# GraphicDisplay.net
KiCad netlist of a schematic drawn in EAGLE
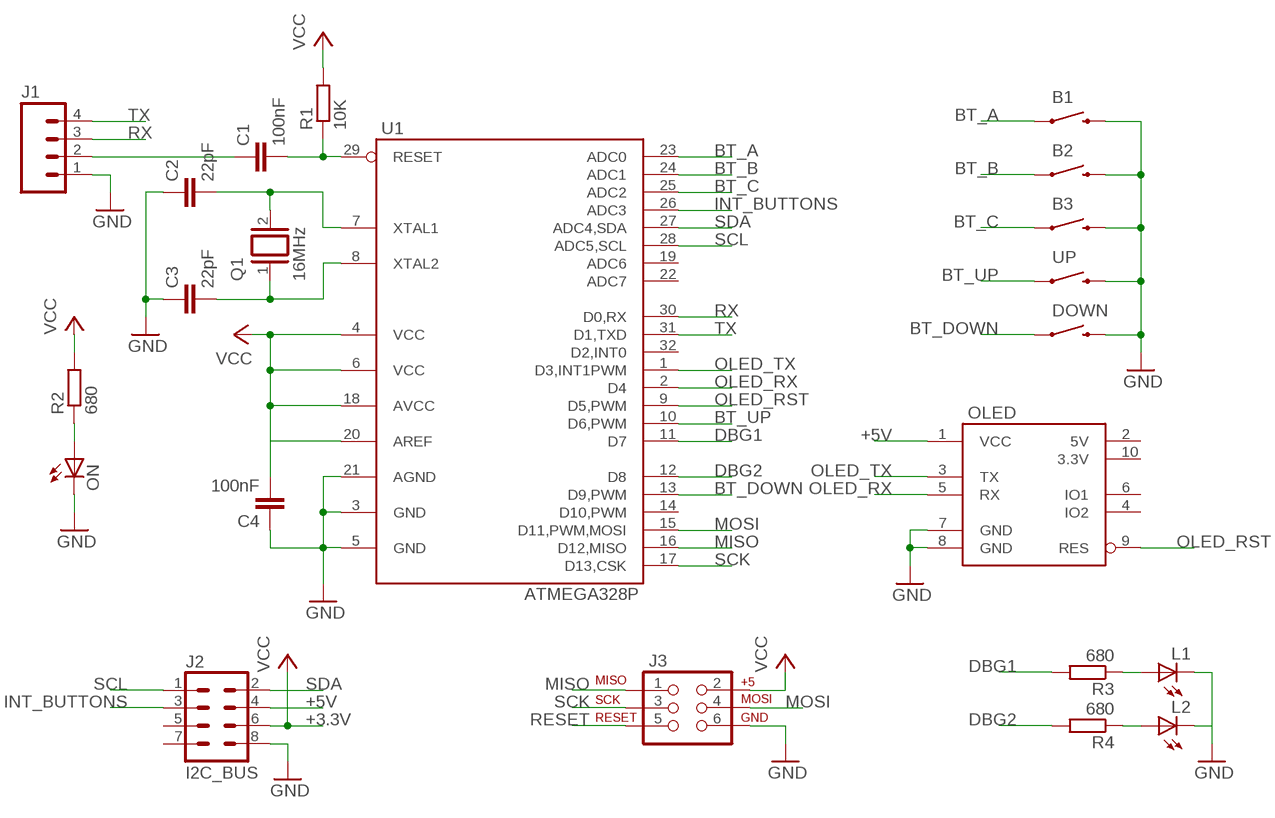
[diagram p0: schematic, sheet 1]

(export (version "E")
  (design (tool "Eeschema 10.0.6"))
  (components
    (comp (ref "B1")
      (value "SWITCH-MOMENTARY-212MM")
      (footprint "eagle-import:TACTILE-PTH-12MM")
      (libsource (lib "eagle-import") (part "SWITCH-MOMENTARY-212MM"))
    )
    (comp (ref "B2")
      (value "SWITCH-MOMENTARY-212MM")
      (footprint "eagle-import:TACTILE-PTH-12MM")
      (libsource (lib "eagle-import") (part "SWITCH-MOMENTARY-212MM"))
    )
    (comp (ref "B3")
      (value "SWITCH-MOMENTARY-212MM")
      (footprint "eagle-import:TACTILE-PTH-12MM")
      (libsource (lib "eagle-import") (part "SWITCH-MOMENTARY-212MM"))
    )
    (comp (ref "C1")
      (value "100nF")
      (footprint "eagle-import:C0805")
      (libsource (lib "eagle-import") (part "C-EUC0805"))
    )
    (comp (ref "C2")
      (value "22pF")
      (footprint "eagle-import:C0805")
      (libsource (lib "eagle-import") (part "C-EUC0805"))
    )
    (comp (ref "C3")
      (value "22pF")
      (footprint "eagle-import:C0805")
      (libsource (lib "eagle-import") (part "C-EUC0805"))
    )
    (comp (ref "C4")
      (value "100nF")
      (footprint "eagle-import:C0805")
      (libsource (lib "eagle-import") (part "C-EUC0805"))
    )
    (comp (ref "DOWN")
      (value "SWITCH-MOMENTARY-212MM")
      (footprint "eagle-import:TACTILE-PTH-12MM")
      (libsource (lib "eagle-import") (part "SWITCH-MOMENTARY-212MM"))
    )
    (comp (ref "J1")
      (value "M04PTH")
      (footprint "eagle-import:1X04")
      (libsource (lib "eagle-import") (part "M04PTH"))
    )
    (comp (ref "J2")
      (value "I2C_BUS")
      (footprint "eagle-import:SOCKET04X2_ANGLE")
      (libsource (lib "eagle-import") (part "IDC-SOCKET04X2IDC_SOCKECT04X2_ANGLE"))
    )
    (comp (ref "J3")
      (value "AVR_SPI_PRG_6NS")
      (footprint "eagle-import:2X3-NS")
      (libsource (lib "eagle-import") (part "AVR_SPI_PRG_6NS"))
    )
    (comp (ref "L1")
      (value "LEDCHIP-LED0805")
      (footprint "eagle-import:CHIP-LED0805")
      (libsource (lib "eagle-import") (part "LEDCHIP-LED0805"))
    )
    (comp (ref "L2")
      (value "LEDCHIP-LED0805")
      (footprint "eagle-import:CHIP-LED0805")
      (libsource (lib "eagle-import") (part "LEDCHIP-LED0805"))
    )
    (comp (ref "OLED")
      (value "UOLED-160-G2")
      (footprint "eagle-import:UOLED-160-G2")
      (libsource (lib "eagle-import") (part "UOLED-160-G2"))
    )
    (comp (ref "ON")
      (value "LEDCHIP-LED0805")
      (footprint "eagle-import:CHIP-LED0805")
      (libsource (lib "eagle-import") (part "LEDCHIP-LED0805"))
    )
    (comp (ref "Q1")
      (value "16MHz")
      (footprint "eagle-import:QS")
      (libsource (lib "eagle-import") (part "XTAL/S"))
    )
    (comp (ref "R1")
      (value "10K")
      (footprint "eagle-import:R0805")
      (libsource (lib "eagle-import") (part "R-EU_R0805"))
    )
    (comp (ref "R2")
      (value "680")
      (footprint "eagle-import:R0805")
      (libsource (lib "eagle-import") (part "R-EU_R0805"))
    )
    (comp (ref "R3")
      (value "680")
      (footprint "eagle-import:R0805")
      (libsource (lib "eagle-import") (part "R-EU_R0805"))
    )
    (comp (ref "R4")
      (value "680")
      (footprint "eagle-import:R0805")
      (libsource (lib "eagle-import") (part "R-EU_R0805"))
    )
    (comp (ref "U1")
      (value "ATMEGA328P")
      (footprint "eagle-import:TQFP32-08")
      (libsource (lib "eagle-import") (part "ATMEGA328-SMT"))
    )
    (comp (ref "UP")
      (value "SWITCH-MOMENTARY-212MM")
      (footprint "eagle-import:TACTILE-PTH-12MM")
      (libsource (lib "eagle-import") (part "SWITCH-MOMENTARY-212MM"))
    )
  )
  (nets
    (net (code "1") (name "/+5V") (class "Default")
      (node (ref "J2") (pin "4") (pinfunction "4_4") (pintype "passive"))
      (node (ref "OLED") (pin "1") (pinfunction "VCC_1") (pintype "power_in"))
    )
    (net (code "2") (name "/3.3V") (class "Default")
      (node (ref "OLED") (pin "10") (pinfunction "3.3V_10") (pintype "power_in"))
    )
    (net (code "3") (name "/5V") (class "Default")
      (node (ref "OLED") (pin "2") (pinfunction "5V_2") (pintype "power_in"))
    )
    (net (code "4") (name "/BT_A") (class "Default")
      (node (ref "B1") (pin "1") (pinfunction "1_1") (pintype "passive"))
      (node (ref "U1") (pin "23") (pinfunction "ADC0_23") (pintype "bidirectional"))
    )
    (net (code "5") (name "/BT_B") (class "Default")
      (node (ref "B2") (pin "1") (pinfunction "1_1") (pintype "passive"))
      (node (ref "U1") (pin "24") (pinfunction "ADC1_24") (pintype "bidirectional"))
    )
    (net (code "6") (name "/BT_C") (class "Default")
      (node (ref "B3") (pin "1") (pinfunction "1_1") (pintype "passive"))
      (node (ref "U1") (pin "25") (pinfunction "ADC2_25") (pintype "bidirectional"))
    )
    (net (code "7") (name "/BT_DOWN") (class "Default")
      (node (ref "DOWN") (pin "1") (pinfunction "1_1") (pintype "passive"))
      (node (ref "U1") (pin "13") (pinfunction "D9,PWM_13") (pintype "bidirectional"))
    )
    (net (code "8") (name "/BT_UP") (class "Default")
      (node (ref "U1") (pin "10") (pinfunction "D6,PWM_10") (pintype "bidirectional"))
      (node (ref "UP") (pin "1") (pinfunction "1_1") (pintype "passive"))
    )
    (net (code "9") (name "/DBG1") (class "Default")
      (node (ref "R3") (pin "2") (pinfunction "2_2") (pintype "passive"))
      (node (ref "U1") (pin "11") (pinfunction "D7_11") (pintype "bidirectional"))
    )
    (net (code "10") (name "/DBG2") (class "Default")
      (node (ref "R4") (pin "2") (pinfunction "2_2") (pintype "passive"))
      (node (ref "U1") (pin "12") (pinfunction "D8_12") (pintype "bidirectional"))
    )
    (net (code "11") (name "/INT_BUTTONS") (class "Default")
      (node (ref "J2") (pin "3") (pinfunction "3_3") (pintype "passive"))
      (node (ref "U1") (pin "26") (pinfunction "ADC3_26") (pintype "bidirectional"))
    )
    (net (code "12") (name "/MISO") (class "Default")
      (node (ref "J3") (pin "1") (pinfunction "1_1") (pintype "passive"))
      (node (ref "U1") (pin "16") (pinfunction "D12,MISO_16") (pintype "bidirectional"))
    )
    (net (code "13") (name "/MOSI") (class "Default")
      (node (ref "J3") (pin "4") (pinfunction "4_4") (pintype "passive"))
      (node (ref "U1") (pin "15") (pinfunction "D11,PWM,MOSI_15") (pintype "bidirectional"))
    )
    (net (code "14") (name "/OLED_RST") (class "Default")
      (node (ref "OLED") (pin "9") (pinfunction "RES_9") (pintype "bidirectional"))
      (node (ref "U1") (pin "9") (pinfunction "D5,PWM_9") (pintype "bidirectional"))
    )
    (net (code "15") (name "/OLED_RX") (class "Default")
      (node (ref "OLED") (pin "5") (pinfunction "RX_5") (pintype "bidirectional"))
      (node (ref "U1") (pin "2") (pinfunction "D4_2") (pintype "bidirectional"))
    )
    (net (code "16") (name "/OLED_TX") (class "Default")
      (node (ref "OLED") (pin "3") (pinfunction "TX_3") (pintype "bidirectional"))
      (node (ref "U1") (pin "1") (pinfunction "D3,INT1PWM_1") (pintype "bidirectional"))
    )
    (net (code "17") (name "/RESET") (class "Default")
      (node (ref "C1") (pin "2") (pinfunction "2_2") (pintype "passive"))
      (node (ref "J3") (pin "5") (pinfunction "5_5") (pintype "passive"))
      (node (ref "R1") (pin "1") (pinfunction "1_1") (pintype "passive"))
      (node (ref "U1") (pin "29") (pinfunction "RESET_29") (pintype "bidirectional"))
    )
    (net (code "18") (name "/RX") (class "Default")
      (node (ref "J1") (pin "3") (pinfunction "3_3") (pintype "passive"))
      (node (ref "U1") (pin "30") (pinfunction "D0,RX_30") (pintype "bidirectional"))
    )
    (net (code "19") (name "/SCK") (class "Default")
      (node (ref "J3") (pin "3") (pinfunction "3_3") (pintype "passive"))
      (node (ref "U1") (pin "17") (pinfunction "D13,CSK_17") (pintype "bidirectional"))
    )
    (net (code "20") (name "/SCL") (class "Default")
      (node (ref "J2") (pin "1") (pinfunction "1_1") (pintype "passive"))
      (node (ref "U1") (pin "28") (pinfunction "ADC5,SCL_28") (pintype "bidirectional"))
    )
    (net (code "21") (name "/SDA") (class "Default")
      (node (ref "J2") (pin "2") (pinfunction "2_2") (pintype "passive"))
      (node (ref "U1") (pin "27") (pinfunction "ADC4,SDA_27") (pintype "bidirectional"))
    )
    (net (code "22") (name "/TX") (class "Default")
      (node (ref "J1") (pin "4") (pinfunction "4_4") (pintype "passive"))
      (node (ref "U1") (pin "31") (pinfunction "D1,TXD_31") (pintype "bidirectional"))
    )
    (net (code "23") (name "GND") (class "Default")
      (node (ref "B1") (pin "3") (pinfunction "2_3") (pintype "passive"))
      (node (ref "B2") (pin "3") (pinfunction "2_3") (pintype "passive"))
      (node (ref "B3") (pin "3") (pinfunction "2_3") (pintype "passive"))
      (node (ref "C2") (pin "1") (pinfunction "1_1") (pintype "passive"))
      (node (ref "C3") (pin "1") (pinfunction "1_1") (pintype "passive"))
      (node (ref "C4") (pin "1") (pinfunction "1_1") (pintype "passive"))
      (node (ref "DOWN") (pin "3") (pinfunction "2_3") (pintype "passive"))
      (node (ref "J1") (pin "1") (pinfunction "1_1") (pintype "passive"))
      (node (ref "J2") (pin "8") (pinfunction "8_8") (pintype "passive"))
      (node (ref "J3") (pin "6") (pinfunction "6_6") (pintype "passive"))
      (node (ref "L1") (pin "C") (pinfunction "C_C") (pintype "passive"))
      (node (ref "L2") (pin "C") (pinfunction "C_C") (pintype "passive"))
      (node (ref "OLED") (pin "7") (pinfunction "GND_7") (pintype "power_in"))
      (node (ref "OLED") (pin "8") (pinfunction "GND_8") (pintype "power_in"))
      (node (ref "ON") (pin "C") (pinfunction "C_C") (pintype "passive"))
      (node (ref "U1") (pin "21") (pinfunction "AGND_21") (pintype "passive"))
      (node (ref "U1") (pin "3") (pinfunction "GND_3") (pintype "power_in"))
      (node (ref "U1") (pin "5") (pinfunction "GND_5") (pintype "power_in"))
      (node (ref "UP") (pin "3") (pinfunction "2_3") (pintype "passive"))
    )
    (net (code "24") (name "Net-(C1-Pad1)") (class "Default")
      (node (ref "C1") (pin "1") (pinfunction "1_1") (pintype "passive"))
      (node (ref "J1") (pin "2") (pinfunction "2_2") (pintype "passive"))
    )
    (net (code "25") (name "Net-(L1-PadA)") (class "Default")
      (node (ref "L1") (pin "A") (pinfunction "A_A") (pintype "passive"))
      (node (ref "R3") (pin "1") (pinfunction "1_1") (pintype "passive"))
    )
    (net (code "26") (name "Net-(L2-PadA)") (class "Default")
      (node (ref "L2") (pin "A") (pinfunction "A_A") (pintype "passive"))
      (node (ref "R4") (pin "1") (pinfunction "1_1") (pintype "passive"))
    )
    (net (code "27") (name "Net-(ON-PadA)") (class "Default")
      (node (ref "ON") (pin "A") (pinfunction "A_A") (pintype "passive"))
      (node (ref "R2") (pin "1") (pinfunction "1_1") (pintype "passive"))
    )
    (net (code "28") (name "Net-(U1-XTAL1)") (class "Default")
      (node (ref "C2") (pin "2") (pinfunction "2_2") (pintype "passive"))
      (node (ref "Q1") (pin "2") (pinfunction "2_2") (pintype "passive"))
      (node (ref "U1") (pin "7") (pinfunction "XTAL1_7") (pintype "bidirectional"))
    )
    (net (code "29") (name "Net-(U1-XTAL2)") (class "Default")
      (node (ref "C3") (pin "2") (pinfunction "2_2") (pintype "passive"))
      (node (ref "Q1") (pin "1") (pinfunction "1_1") (pintype "passive"))
      (node (ref "U1") (pin "8") (pinfunction "XTAL2_8") (pintype "bidirectional"))
    )
    (net (code "30") (name "VCC") (class "Default")
      (node (ref "C4") (pin "2") (pinfunction "2_2") (pintype "passive"))
      (node (ref "J2") (pin "6") (pinfunction "6_6") (pintype "passive"))
      (node (ref "J3") (pin "2") (pinfunction "2_2") (pintype "passive"))
      (node (ref "R1") (pin "2") (pinfunction "2_2") (pintype "passive"))
      (node (ref "R2") (pin "2") (pinfunction "2_2") (pintype "passive"))
      (node (ref "U1") (pin "18") (pinfunction "AVCC_18") (pintype "passive"))
      (node (ref "U1") (pin "20") (pinfunction "AREF_20") (pintype "passive"))
      (node (ref "U1") (pin "4") (pinfunction "VCC_4") (pintype "power_in"))
      (node (ref "U1") (pin "6") (pinfunction "VCC_6") (pintype "power_in"))
    )
    (net (code "31") (name "unconnected-(J2-Pad5)") (class "Default")
      (node (ref "J2") (pin "5") (pinfunction "5_5") (pintype "passive"))
    )
    (net (code "32") (name "unconnected-(J2-Pad7)") (class "Default")
      (node (ref "J2") (pin "7") (pinfunction "7_7") (pintype "passive"))
    )
    (net (code "33") (name "unconnected-(OLED-IO1-Pad6)") (class "Default")
      (node (ref "OLED") (pin "6") (pinfunction "IO1_6") (pintype "bidirectional"))
    )
    (net (code "34") (name "unconnected-(OLED-IO2-Pad4)") (class "Default")
      (node (ref "OLED") (pin "4") (pinfunction "IO2_4") (pintype "bidirectional"))
    )
    (net (code "35") (name "unconnected-(U1-ADC6-Pad19)") (class "Default")
      (node (ref "U1") (pin "19") (pinfunction "ADC6_19") (pintype "bidirectional"))
    )
    (net (code "36") (name "unconnected-(U1-ADC7-Pad22)") (class "Default")
      (node (ref "U1") (pin "22") (pinfunction "ADC7_22") (pintype "bidirectional"))
    )
    (net (code "37") (name "unconnected-(U1-D2,INT0-Pad32)") (class "Default")
      (node (ref "U1") (pin "32") (pinfunction "D2,INT0_32") (pintype "bidirectional"))
    )
    (net (code "38") (name "unconnected-(U1-D10,PWM-Pad14)") (class "Default")
      (node (ref "U1") (pin "14") (pinfunction "D10,PWM_14") (pintype "bidirectional"))
    )
  )
)
